# Adafruit_proto_pi_plate.net
KiCad netlist of a schematic drawn in EAGLE
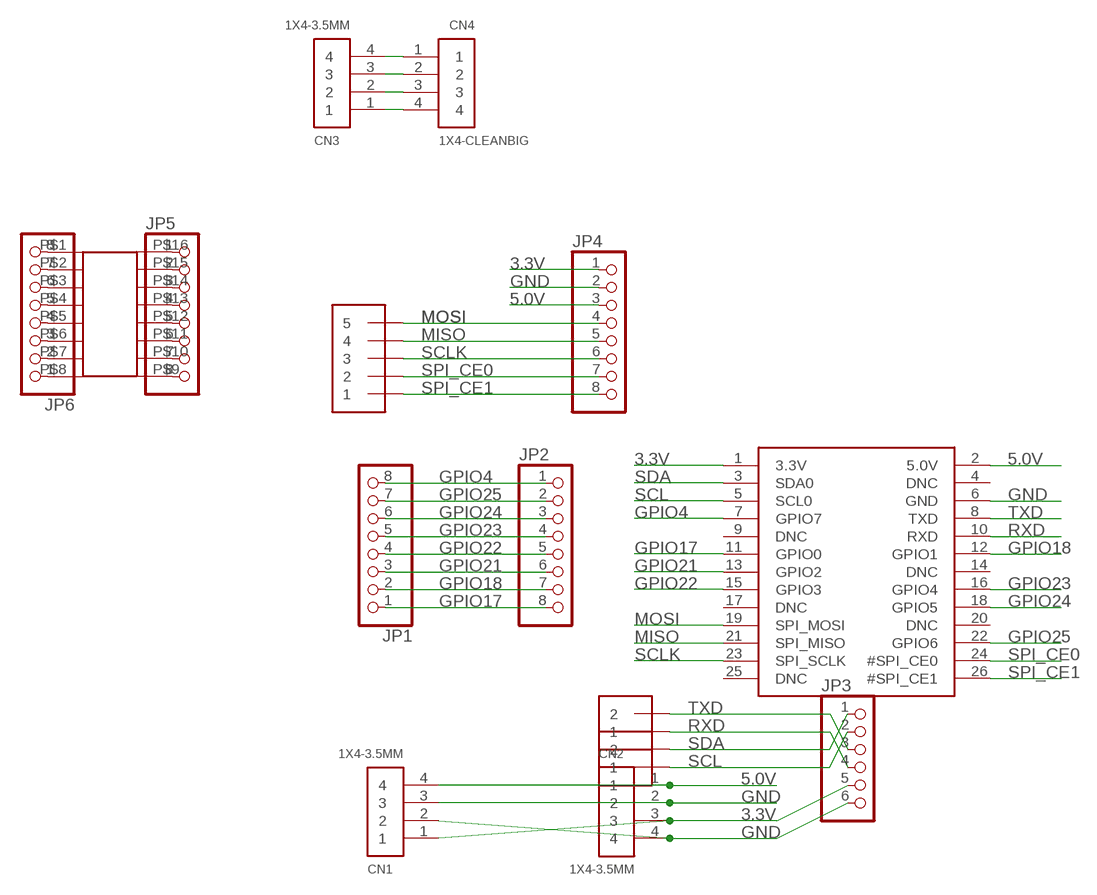
[diagram p0: schematic, sheet 1]

(export (version "E")
  (design (tool "Eeschema 10.0.6"))
  (components
    (comp (ref "CN1")
      (value "1X4-3.5MM")
      (footprint "eagle-import:1X04-3.5MM")
      (libsource (lib "eagle-import") (part "1X4-3.5MM"))
    )
    (comp (ref "CN2")
      (value "1X4-3.5MM")
      (footprint "eagle-import:1X04-3.5MM")
      (libsource (lib "eagle-import") (part "1X4-3.5MM"))
    )
    (comp (ref "CN3")
      (value "1X4-3.5MM")
      (footprint "eagle-import:1X04-3.5MM")
      (libsource (lib "eagle-import") (part "1X4-3.5MM"))
    )
    (comp (ref "CN4")
      (value "1X4-CLEANBIG")
      (footprint "eagle-import:1X04-CLEANBIG")
      (libsource (lib "eagle-import") (part "1X4-CLEANBIG"))
    )
    (comp (ref "J1")
      (value "1X2-3.5MM")
      (footprint "eagle-import:1X2-3.5MM")
      (libsource (lib "eagle-import") (part "1X2-3.5MM"))
    )
    (comp (ref "J2")
      (value "1X2-3.5MM")
      (footprint "eagle-import:1X2-3.5MM")
      (libsource (lib "eagle-import") (part "1X2-3.5MM"))
    )
    (comp (ref "J3")
      (value "1X5")
      (footprint "eagle-import:1X05-3.5MM")
      (libsource (lib "eagle-import") (part "1X5"))
    )
    (comp (ref "JP1")
      (value "PINHD-1X8-3.5MM")
      (footprint "eagle-import:1X08-3.5MM")
      (libsource (lib "eagle-import") (part "PINHD-1X8-3.5MM"))
    )
    (comp (ref "JP2")
      (value "PINHD-1X8BIG")
      (footprint "eagle-import:1X08-BIG")
      (libsource (lib "eagle-import") (part "PINHD-1X8BIG"))
    )
    (comp (ref "JP3")
      (value "PINHD-1X6B")
      (footprint "eagle-import:1X06-BIG")
      (libsource (lib "eagle-import") (part "PINHD-1X6B"))
    )
    (comp (ref "JP4")
      (value "PINHD-1X8BIG")
      (footprint "eagle-import:1X08-BIG")
      (libsource (lib "eagle-import") (part "PINHD-1X8BIG"))
    )
    (comp (ref "JP5")
      (value "PINHD-1X8BIG")
      (footprint "eagle-import:1X08-BIG")
      (libsource (lib "eagle-import") (part "PINHD-1X8BIG"))
    )
    (comp (ref "JP6")
      (value "PINHD-1X8BIG")
      (footprint "eagle-import:1X08-BIG")
      (libsource (lib "eagle-import") (part "PINHD-1X8BIG"))
    )
    (comp (ref "U$1")
      (value "RASPBERRYPI_BB")
      (footprint "eagle-import:RASBERRYPI_SHIELD")
      (libsource (lib "eagle-import") (part "RASPBERRYPI_BB"))
    )
    (comp (ref "U$2")
      (value "SMD-16SOIC")
      (footprint "eagle-import:SO-16NMW")
      (libsource (lib "eagle-import") (part "SMD-16SOIC"))
    )
  )
  (nets
    (net (code "1") (name "/3.3V") (class "Default")
      (node (ref "CN1") (pin "1") (pinfunction "1_1") (pintype "bidirectional"))
      (node (ref "CN2") (pin "3") (pinfunction "3_3") (pintype "bidirectional"))
      (node (ref "JP3") (pin "5") (pinfunction "5_5") (pintype "passive"))
      (node (ref "JP4") (pin "1") (pinfunction "1_1") (pintype "passive"))
      (node (ref "U$1") (pin "1") (pinfunction "3.3V_1") (pintype "power_in"))
    )
    (net (code "2") (name "/5.0V") (class "Default")
      (node (ref "CN1") (pin "4") (pinfunction "4_4") (pintype "bidirectional"))
      (node (ref "CN2") (pin "1") (pinfunction "1_1") (pintype "bidirectional"))
      (node (ref "JP4") (pin "3") (pinfunction "3_3") (pintype "passive"))
      (node (ref "U$1") (pin "2") (pinfunction "5.0V_2") (pintype "power_in"))
    )
    (net (code "3") (name "/GND") (class "Default")
      (node (ref "CN1") (pin "2") (pinfunction "2_2") (pintype "bidirectional"))
      (node (ref "CN1") (pin "3") (pinfunction "3_3") (pintype "bidirectional"))
      (node (ref "CN2") (pin "2") (pinfunction "2_2") (pintype "bidirectional"))
      (node (ref "CN2") (pin "4") (pinfunction "4_4") (pintype "bidirectional"))
      (node (ref "JP3") (pin "6") (pinfunction "6_6") (pintype "passive"))
      (node (ref "JP4") (pin "2") (pinfunction "2_2") (pintype "passive"))
      (node (ref "U$1") (pin "6") (pinfunction "GND_6") (pintype "power_in"))
    )
    (net (code "4") (name "/GPIO4") (class "Default")
      (node (ref "JP1") (pin "8") (pinfunction "8_8") (pintype "passive"))
      (node (ref "JP2") (pin "1") (pinfunction "1_1") (pintype "passive"))
      (node (ref "U$1") (pin "7") (pinfunction "GPIO7_7") (pintype "bidirectional"))
    )
    (net (code "5") (name "/GPIO17") (class "Default")
      (node (ref "JP1") (pin "1") (pinfunction "1_1") (pintype "passive"))
      (node (ref "JP2") (pin "8") (pinfunction "8_8") (pintype "passive"))
      (node (ref "U$1") (pin "11") (pinfunction "GPIO0_11") (pintype "bidirectional"))
    )
    (net (code "6") (name "/GPIO18") (class "Default")
      (node (ref "JP1") (pin "2") (pinfunction "2_2") (pintype "passive"))
      (node (ref "JP2") (pin "7") (pinfunction "7_7") (pintype "passive"))
      (node (ref "U$1") (pin "12") (pinfunction "GPIO1_12") (pintype "bidirectional"))
    )
    (net (code "7") (name "/GPIO21") (class "Default")
      (node (ref "JP1") (pin "3") (pinfunction "3_3") (pintype "passive"))
      (node (ref "JP2") (pin "6") (pinfunction "6_6") (pintype "passive"))
      (node (ref "U$1") (pin "13") (pinfunction "GPIO2_13") (pintype "bidirectional"))
    )
    (net (code "8") (name "/GPIO22") (class "Default")
      (node (ref "JP1") (pin "4") (pinfunction "4_4") (pintype "passive"))
      (node (ref "JP2") (pin "5") (pinfunction "5_5") (pintype "passive"))
      (node (ref "U$1") (pin "15") (pinfunction "GPIO3_15") (pintype "bidirectional"))
    )
    (net (code "9") (name "/GPIO23") (class "Default")
      (node (ref "JP1") (pin "5") (pinfunction "5_5") (pintype "passive"))
      (node (ref "JP2") (pin "4") (pinfunction "4_4") (pintype "passive"))
      (node (ref "U$1") (pin "16") (pinfunction "GPIO4_16") (pintype "bidirectional"))
    )
    (net (code "10") (name "/GPIO24") (class "Default")
      (node (ref "JP1") (pin "6") (pinfunction "6_6") (pintype "passive"))
      (node (ref "JP2") (pin "3") (pinfunction "3_3") (pintype "passive"))
      (node (ref "U$1") (pin "18") (pinfunction "GPIO5_18") (pintype "bidirectional"))
    )
    (net (code "11") (name "/GPIO25") (class "Default")
      (node (ref "JP1") (pin "7") (pinfunction "7_7") (pintype "passive"))
      (node (ref "JP2") (pin "2") (pinfunction "2_2") (pintype "passive"))
      (node (ref "U$1") (pin "22") (pinfunction "GPIO6_22") (pintype "bidirectional"))
    )
    (net (code "12") (name "/MISO") (class "Default")
      (node (ref "J3") (pin "4") (pinfunction "4_4") (pintype "passive"))
      (node (ref "JP4") (pin "5") (pinfunction "5_5") (pintype "passive"))
      (node (ref "U$1") (pin "21") (pinfunction "SPI_MISO_21") (pintype "input"))
    )
    (net (code "13") (name "/MOSI") (class "Default")
      (node (ref "J3") (pin "5") (pinfunction "5_5") (pintype "passive"))
      (node (ref "JP4") (pin "4") (pinfunction "4_4") (pintype "passive"))
      (node (ref "U$1") (pin "19") (pinfunction "SPI_MOSI_19") (pintype "output"))
    )
    (net (code "14") (name "/RXD") (class "Default")
      (node (ref "J2") (pin "1") (pinfunction "1_1") (pintype "passive"))
      (node (ref "JP3") (pin "4") (pinfunction "4_4") (pintype "passive"))
      (node (ref "U$1") (pin "10") (pinfunction "RXD_10") (pintype "input"))
    )
    (net (code "15") (name "/SCL") (class "Default")
      (node (ref "J1") (pin "1") (pinfunction "1_1") (pintype "passive"))
      (node (ref "JP3") (pin "2") (pinfunction "2_2") (pintype "passive"))
      (node (ref "U$1") (pin "5") (pinfunction "SCL0_5") (pintype "output"))
    )
    (net (code "16") (name "/SCLK") (class "Default")
      (node (ref "J3") (pin "3") (pinfunction "3_3") (pintype "passive"))
      (node (ref "JP4") (pin "6") (pinfunction "6_6") (pintype "passive"))
      (node (ref "U$1") (pin "23") (pinfunction "SPI_SCLK_23") (pintype "output"))
    )
    (net (code "17") (name "/SDA") (class "Default")
      (node (ref "J1") (pin "2") (pinfunction "2_2") (pintype "passive"))
      (node (ref "JP3") (pin "1") (pinfunction "1_1") (pintype "passive"))
      (node (ref "U$1") (pin "3") (pinfunction "SDA0_3") (pintype "bidirectional"))
    )
    (net (code "18") (name "/SPI_CE0") (class "Default")
      (node (ref "J3") (pin "2") (pinfunction "2_2") (pintype "passive"))
      (node (ref "JP4") (pin "7") (pinfunction "7_7") (pintype "passive"))
      (node (ref "U$1") (pin "24") (pinfunction "#SPI_CE0_24") (pintype "output"))
    )
    (net (code "19") (name "/SPI_CE1") (class "Default")
      (node (ref "J3") (pin "1") (pinfunction "1_1") (pintype "passive"))
      (node (ref "JP4") (pin "8") (pinfunction "8_8") (pintype "passive"))
      (node (ref "U$1") (pin "26") (pinfunction "#SPI_CE1_26") (pintype "output"))
    )
    (net (code "20") (name "/TXD") (class "Default")
      (node (ref "J2") (pin "2") (pinfunction "2_2") (pintype "passive"))
      (node (ref "JP3") (pin "3") (pinfunction "3_3") (pintype "passive"))
      (node (ref "U$1") (pin "8") (pinfunction "TXD_8") (pintype "output"))
    )
    (net (code "21") (name "Net-(CN3-Pad1)") (class "Default")
      (node (ref "CN3") (pin "1") (pinfunction "1_1") (pintype "bidirectional"))
      (node (ref "CN4") (pin "4") (pinfunction "4_4") (pintype "bidirectional"))
    )
    (net (code "22") (name "Net-(CN3-Pad2)") (class "Default")
      (node (ref "CN3") (pin "2") (pinfunction "2_2") (pintype "bidirectional"))
      (node (ref "CN4") (pin "3") (pinfunction "3_3") (pintype "bidirectional"))
    )
    (net (code "23") (name "Net-(CN3-Pad3)") (class "Default")
      (node (ref "CN3") (pin "3") (pinfunction "3_3") (pintype "bidirectional"))
      (node (ref "CN4") (pin "2") (pinfunction "2_2") (pintype "bidirectional"))
    )
    (net (code "24") (name "Net-(CN3-Pad4)") (class "Default")
      (node (ref "CN3") (pin "4") (pinfunction "4_4") (pintype "bidirectional"))
      (node (ref "CN4") (pin "1") (pinfunction "1_1") (pintype "bidirectional"))
    )
    (net (code "25") (name "Net-(JP5-Pad1)") (class "Default")
      (node (ref "JP5") (pin "1") (pinfunction "1_1") (pintype "passive"))
      (node (ref "U$2") (pin "P$16") (pinfunction "P$16_P$16") (pintype "bidirectional"))
    )
    (net (code "26") (name "Net-(JP5-Pad2)") (class "Default")
      (node (ref "JP5") (pin "2") (pinfunction "2_2") (pintype "passive"))
      (node (ref "U$2") (pin "P$15") (pinfunction "P$15_P$15") (pintype "bidirectional"))
    )
    (net (code "27") (name "Net-(JP5-Pad3)") (class "Default")
      (node (ref "JP5") (pin "3") (pinfunction "3_3") (pintype "passive"))
      (node (ref "U$2") (pin "P$14") (pinfunction "P$14_P$14") (pintype "bidirectional"))
    )
    (net (code "28") (name "Net-(JP5-Pad4)") (class "Default")
      (node (ref "JP5") (pin "4") (pinfunction "4_4") (pintype "passive"))
      (node (ref "U$2") (pin "P$13") (pinfunction "P$13_P$13") (pintype "bidirectional"))
    )
    (net (code "29") (name "Net-(JP5-Pad5)") (class "Default")
      (node (ref "JP5") (pin "5") (pinfunction "5_5") (pintype "passive"))
      (node (ref "U$2") (pin "P$12") (pinfunction "P$12_P$12") (pintype "bidirectional"))
    )
    (net (code "30") (name "Net-(JP5-Pad6)") (class "Default")
      (node (ref "JP5") (pin "6") (pinfunction "6_6") (pintype "passive"))
      (node (ref "U$2") (pin "P$11") (pinfunction "P$11_P$11") (pintype "bidirectional"))
    )
    (net (code "31") (name "Net-(JP5-Pad7)") (class "Default")
      (node (ref "JP5") (pin "7") (pinfunction "7_7") (pintype "passive"))
      (node (ref "U$2") (pin "P$10") (pinfunction "P$10_P$10") (pintype "bidirectional"))
    )
    (net (code "32") (name "Net-(JP5-Pad8)") (class "Default")
      (node (ref "JP5") (pin "8") (pinfunction "8_8") (pintype "passive"))
      (node (ref "U$2") (pin "P$9") (pinfunction "P$9_P$9") (pintype "bidirectional"))
    )
    (net (code "33") (name "Net-(JP6-Pad1)") (class "Default")
      (node (ref "JP6") (pin "1") (pinfunction "1_1") (pintype "passive"))
      (node (ref "U$2") (pin "P$8") (pinfunction "P$8_P$8") (pintype "bidirectional"))
    )
    (net (code "34") (name "Net-(JP6-Pad2)") (class "Default")
      (node (ref "JP6") (pin "2") (pinfunction "2_2") (pintype "passive"))
      (node (ref "U$2") (pin "P$7") (pinfunction "P$7_P$7") (pintype "bidirectional"))
    )
    (net (code "35") (name "Net-(JP6-Pad3)") (class "Default")
      (node (ref "JP6") (pin "3") (pinfunction "3_3") (pintype "passive"))
      (node (ref "U$2") (pin "P$6") (pinfunction "P$6_P$6") (pintype "bidirectional"))
    )
    (net (code "36") (name "Net-(JP6-Pad4)") (class "Default")
      (node (ref "JP6") (pin "4") (pinfunction "4_4") (pintype "passive"))
      (node (ref "U$2") (pin "P$5") (pinfunction "P$5_P$5") (pintype "bidirectional"))
    )
    (net (code "37") (name "Net-(JP6-Pad5)") (class "Default")
      (node (ref "JP6") (pin "5") (pinfunction "5_5") (pintype "passive"))
      (node (ref "U$2") (pin "P$4") (pinfunction "P$4_P$4") (pintype "bidirectional"))
    )
    (net (code "38") (name "Net-(JP6-Pad6)") (class "Default")
      (node (ref "JP6") (pin "6") (pinfunction "6_6") (pintype "passive"))
      (node (ref "U$2") (pin "P$3") (pinfunction "P$3_P$3") (pintype "bidirectional"))
    )
    (net (code "39") (name "Net-(JP6-Pad7)") (class "Default")
      (node (ref "JP6") (pin "7") (pinfunction "7_7") (pintype "passive"))
      (node (ref "U$2") (pin "P$2") (pinfunction "P$2_P$2") (pintype "bidirectional"))
    )
    (net (code "40") (name "Net-(JP6-Pad8)") (class "Default")
      (node (ref "JP6") (pin "8") (pinfunction "8_8") (pintype "passive"))
      (node (ref "U$2") (pin "P$1") (pinfunction "P$1_P$1") (pintype "bidirectional"))
    )
    (net (code "41") (name "unconnected-(U$1-DNC-Pad4)") (class "Default")
      (node (ref "U$1") (pin "4") (pinfunction "DNC_4") (pintype "no_connect"))
    )
    (net (code "42") (name "unconnected-(U$1-DNC-Pad9)") (class "Default")
      (node (ref "U$1") (pin "9") (pinfunction "DNC_9") (pintype "no_connect"))
    )
    (net (code "43") (name "unconnected-(U$1-DNC-Pad14)") (class "Default")
      (node (ref "U$1") (pin "14") (pinfunction "DNC_14") (pintype "no_connect"))
    )
    (net (code "44") (name "unconnected-(U$1-DNC-Pad17)") (class "Default")
      (node (ref "U$1") (pin "17") (pinfunction "DNC_17") (pintype "no_connect"))
    )
    (net (code "45") (name "unconnected-(U$1-DNC-Pad20)") (class "Default")
      (node (ref "U$1") (pin "20") (pinfunction "DNC_20") (pintype "no_connect"))
    )
    (net (code "46") (name "unconnected-(U$1-DNC-Pad25)") (class "Default")
      (node (ref "U$1") (pin "25") (pinfunction "DNC_25") (pintype "no_connect"))
    )
  )
)
